# merkur-osdgruve-42.net
KiCad netlist of a schematic drawn in EAGLE
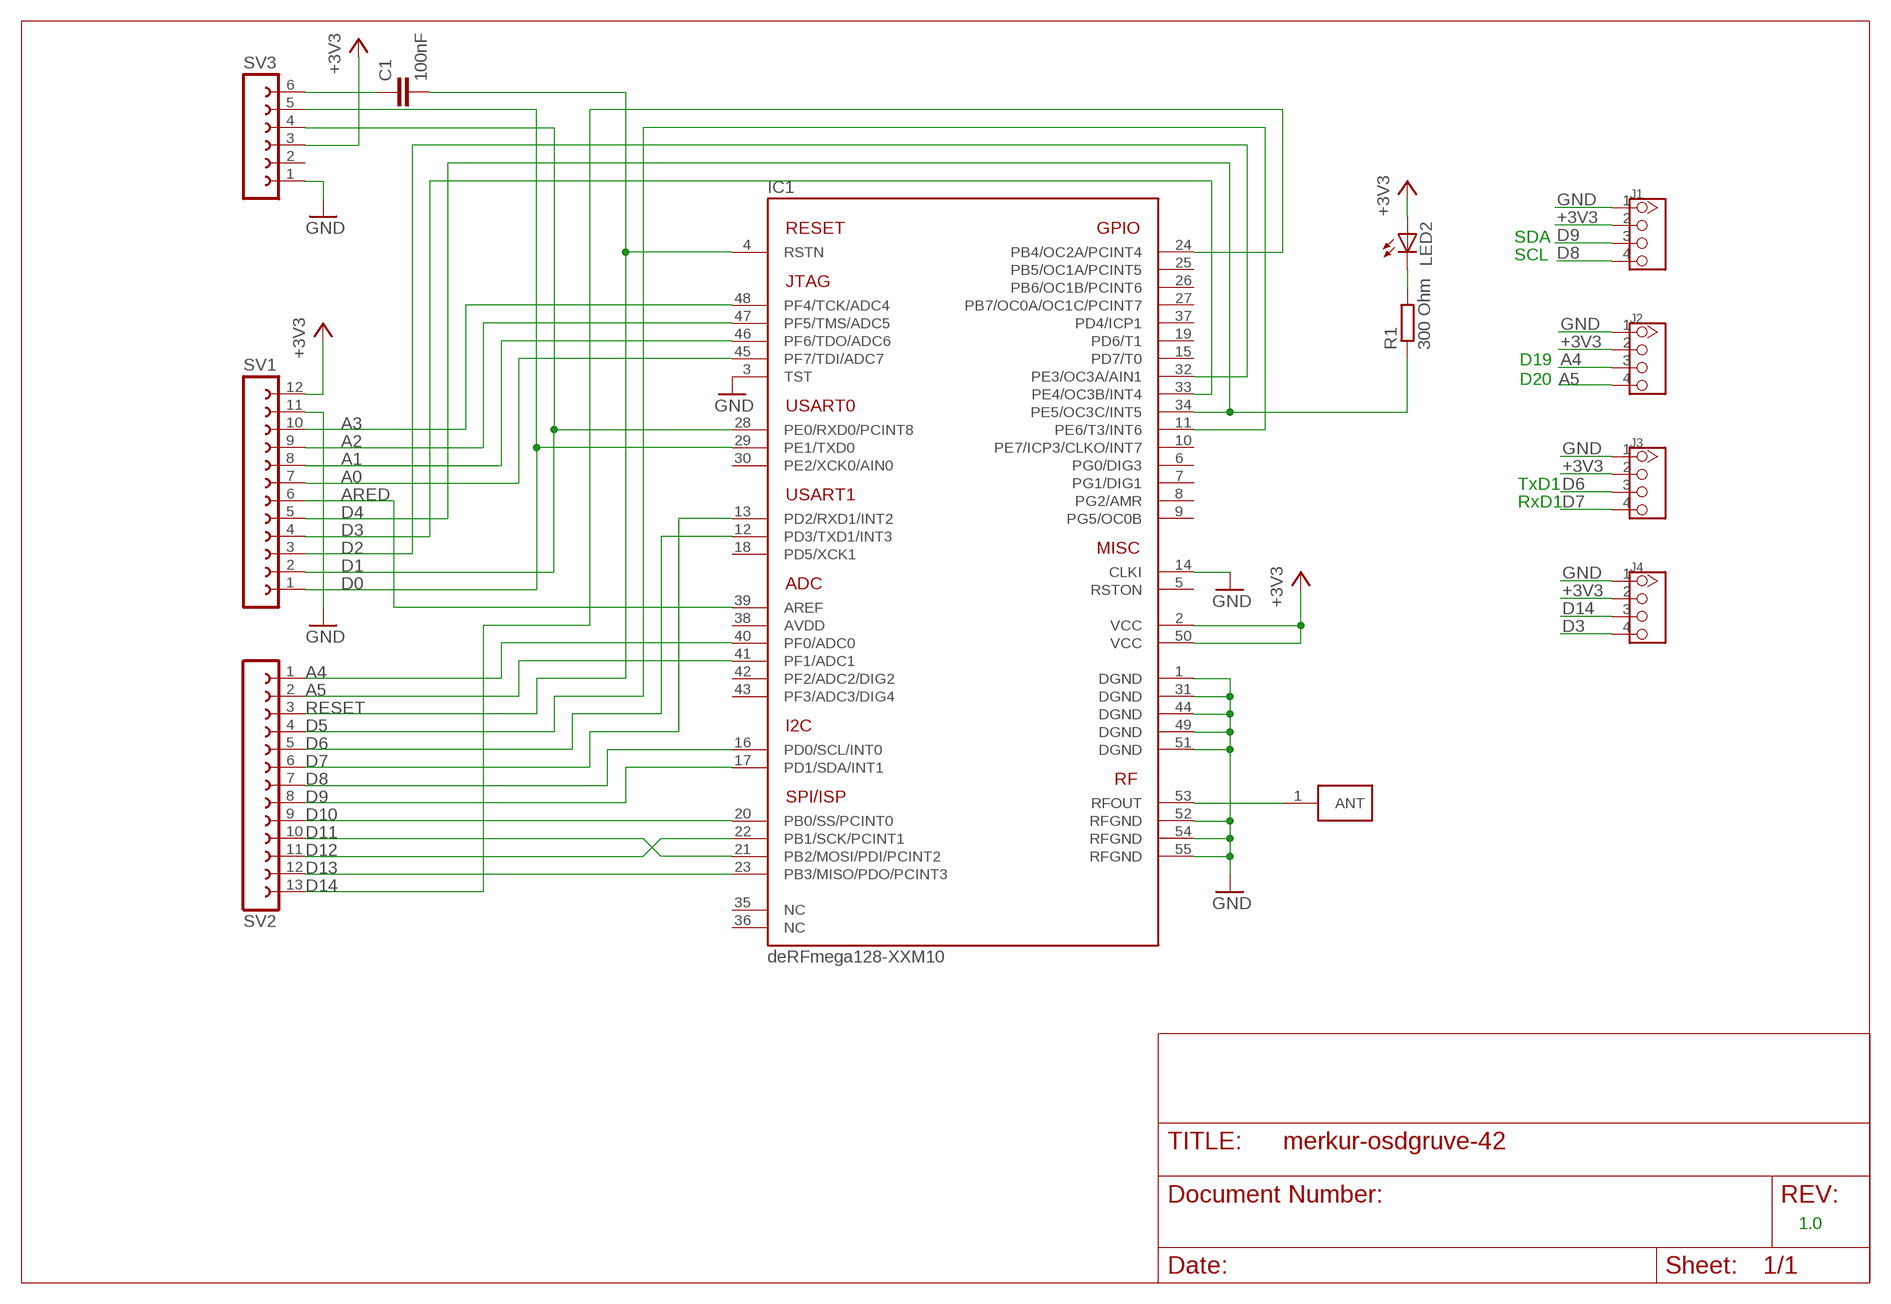
[diagram p0: schematic, sheet 1]

(export (version "E")
  (design (tool "Eeschema 10.0.6"))
  (components
    (comp (ref "C1")
      (value "100nF")
      (footprint "eagle-import:C0603")
      (libsource (lib "eagle-import") (part "C-EUC0603"))
    )
    (comp (ref "IC1")
      (value "DERFMEGA128-XXM10")
      (footprint "eagle-import:A-M10")
      (libsource (lib "eagle-import") (part "DERFMEGA128-XXM10"))
    )
    (comp (ref "J1")
      (value "CONNECTOR_TWIG-4P-2.0-2.0")
      (footprint "eagle-import:CONNECTOR_4P-2.0")
      (libsource (lib "eagle-import") (part "CONNECTOR_TWIG-4P-2.0-2.0"))
    )
    (comp (ref "J2")
      (value "CONNECTOR_TWIG-4P-2.0-2.0")
      (footprint "eagle-import:CONNECTOR_4P-2.0")
      (libsource (lib "eagle-import") (part "CONNECTOR_TWIG-4P-2.0-2.0"))
    )
    (comp (ref "J3")
      (value "CONNECTOR_TWIG-4P-2.0-2.0")
      (footprint "eagle-import:CONNECTOR_4P-2.0")
      (libsource (lib "eagle-import") (part "CONNECTOR_TWIG-4P-2.0-2.0"))
    )
    (comp (ref "J4")
      (value "CONNECTOR_TWIG-4P-2.0-2.0")
      (footprint "eagle-import:CONNECTOR_4P-2.0")
      (libsource (lib "eagle-import") (part "CONNECTOR_TWIG-4P-2.0-2.0"))
    )
    (comp (ref "LED2")
      (value "LEDCHIP-LED0603")
      (footprint "eagle-import:CHIP-LED0603")
      (libsource (lib "eagle-import") (part "LEDCHIP-LED0603"))
    )
    (comp (ref "R1")
      (value "300 Ohm")
      (footprint "eagle-import:R0603")
      (libsource (lib "eagle-import") (part "R-EU_R0603"))
    )
    (comp (ref "SV1")
      (value "FE12-1")
      (footprint "eagle-import:FE12")
      (libsource (lib "eagle-import") (part "FE12-1"))
    )
    (comp (ref "SV2")
      (value "FE13-1")
      (footprint "eagle-import:FE13")
      (libsource (lib "eagle-import") (part "FE13-1"))
    )
    (comp (ref "SV3")
      (value "FE06-1")
      (footprint "eagle-import:FE06")
      (libsource (lib "eagle-import") (part "FE06-1"))
    )
    (comp (ref "U$1")
      (value "PAD")
      (footprint "eagle-import:FE05-1")
      (libsource (lib "eagle-import") (part "PAD"))
    )
  )
  (nets
    (net (code "1") (name "+3V3") (class "Default")
      (node (ref "IC1") (pin "2") (pinfunction "VCC_2") (pintype "power_in"))
      (node (ref "IC1") (pin "50") (pinfunction "VCC_50") (pintype "power_in"))
      (node (ref "J1") (pin "2") (pinfunction "2_2") (pintype "bidirectional"))
      (node (ref "J2") (pin "2") (pinfunction "2_2") (pintype "bidirectional"))
      (node (ref "J3") (pin "2") (pinfunction "2_2") (pintype "bidirectional"))
      (node (ref "J4") (pin "2") (pinfunction "2_2") (pintype "bidirectional"))
      (node (ref "LED2") (pin "A") (pinfunction "A_A") (pintype "passive"))
      (node (ref "SV1") (pin "12") (pinfunction "12_12") (pintype "passive"))
      (node (ref "SV3") (pin "3") (pinfunction "3_3") (pintype "passive"))
    )
    (net (code "2") (name "/A0") (class "Default")
      (node (ref "IC1") (pin "45") (pinfunction "PF7/TDI/ADC7_45") (pintype "bidirectional"))
      (node (ref "SV1") (pin "7") (pinfunction "7_7") (pintype "passive"))
    )
    (net (code "3") (name "/A1") (class "Default")
      (node (ref "IC1") (pin "46") (pinfunction "PF6/TDO/ADC6_46") (pintype "bidirectional"))
      (node (ref "SV1") (pin "8") (pinfunction "8_8") (pintype "passive"))
    )
    (net (code "4") (name "/A2") (class "Default")
      (node (ref "IC1") (pin "47") (pinfunction "PF5/TMS/ADC5_47") (pintype "bidirectional"))
      (node (ref "SV1") (pin "9") (pinfunction "9_9") (pintype "passive"))
    )
    (net (code "5") (name "/A3") (class "Default")
      (node (ref "IC1") (pin "48") (pinfunction "PF4/TCK/ADC4_48") (pintype "bidirectional"))
      (node (ref "SV1") (pin "10") (pinfunction "10_10") (pintype "passive"))
    )
    (net (code "6") (name "/A4") (class "Default")
      (node (ref "IC1") (pin "40") (pinfunction "PF0/ADC0_40") (pintype "bidirectional"))
      (node (ref "J2") (pin "3") (pinfunction "3_3") (pintype "bidirectional"))
      (node (ref "SV2") (pin "1") (pinfunction "1_1") (pintype "passive"))
    )
    (net (code "7") (name "/A5") (class "Default")
      (node (ref "IC1") (pin "41") (pinfunction "PF1/ADC1_41") (pintype "bidirectional"))
      (node (ref "J2") (pin "4") (pinfunction "4_4") (pintype "bidirectional"))
      (node (ref "SV2") (pin "2") (pinfunction "2_2") (pintype "passive"))
    )
    (net (code "8") (name "/ARED") (class "Default")
      (node (ref "IC1") (pin "39") (pinfunction "AREF_39") (pintype "bidirectional"))
      (node (ref "SV1") (pin "6") (pinfunction "6_6") (pintype "passive"))
    )
    (net (code "9") (name "/AVDD") (class "Default")
      (node (ref "IC1") (pin "38") (pinfunction "AVDD_38") (pintype "power_in"))
    )
    (net (code "10") (name "/D0") (class "Default")
      (node (ref "IC1") (pin "29") (pinfunction "PE1/TXD0_29") (pintype "bidirectional"))
      (node (ref "SV1") (pin "1") (pinfunction "1_1") (pintype "passive"))
      (node (ref "SV3") (pin "5") (pinfunction "5_5") (pintype "passive"))
    )
    (net (code "11") (name "/D1") (class "Default")
      (node (ref "IC1") (pin "28") (pinfunction "PE0/RXD0/PCINT8_28") (pintype "bidirectional"))
      (node (ref "SV1") (pin "2") (pinfunction "2_2") (pintype "passive"))
      (node (ref "SV3") (pin "4") (pinfunction "4_4") (pintype "passive"))
    )
    (net (code "12") (name "/D2") (class "Default")
      (node (ref "IC1") (pin "32") (pinfunction "PE3/OC3A/AIN1_32") (pintype "bidirectional"))
      (node (ref "SV1") (pin "3") (pinfunction "3_3") (pintype "passive"))
    )
    (net (code "13") (name "/D3") (class "Default")
      (node (ref "IC1") (pin "33") (pinfunction "PE4/OC3B/INT4_33") (pintype "bidirectional"))
      (node (ref "J4") (pin "4") (pinfunction "4_4") (pintype "bidirectional"))
      (node (ref "SV1") (pin "4") (pinfunction "4_4") (pintype "passive"))
    )
    (net (code "14") (name "/D4") (class "Default")
      (node (ref "IC1") (pin "34") (pinfunction "PE5/OC3C/INT5_34") (pintype "bidirectional"))
      (node (ref "R1") (pin "1") (pinfunction "1_1") (pintype "passive"))
      (node (ref "SV1") (pin "5") (pinfunction "5_5") (pintype "passive"))
    )
    (net (code "15") (name "/D5") (class "Default")
      (node (ref "IC1") (pin "11") (pinfunction "PE6/T3/INT6_11") (pintype "bidirectional"))
      (node (ref "SV2") (pin "4") (pinfunction "4_4") (pintype "passive"))
    )
    (net (code "16") (name "/D6") (class "Default")
      (node (ref "IC1") (pin "12") (pinfunction "PD3/TXD1/INT3_12") (pintype "bidirectional"))
      (node (ref "J3") (pin "3") (pinfunction "3_3") (pintype "bidirectional"))
      (node (ref "SV2") (pin "5") (pinfunction "5_5") (pintype "passive"))
    )
    (net (code "17") (name "/D7") (class "Default")
      (node (ref "IC1") (pin "13") (pinfunction "PD2/RXD1/INT2_13") (pintype "bidirectional"))
      (node (ref "J3") (pin "4") (pinfunction "4_4") (pintype "bidirectional"))
      (node (ref "SV2") (pin "6") (pinfunction "6_6") (pintype "passive"))
    )
    (net (code "18") (name "/D8") (class "Default")
      (node (ref "IC1") (pin "16") (pinfunction "PD0/SCL/INT0_16") (pintype "bidirectional"))
      (node (ref "J1") (pin "4") (pinfunction "4_4") (pintype "bidirectional"))
      (node (ref "SV2") (pin "7") (pinfunction "7_7") (pintype "passive"))
    )
    (net (code "19") (name "/D9") (class "Default")
      (node (ref "IC1") (pin "17") (pinfunction "PD1/SDA/INT1_17") (pintype "bidirectional"))
      (node (ref "J1") (pin "3") (pinfunction "3_3") (pintype "bidirectional"))
      (node (ref "SV2") (pin "8") (pinfunction "8_8") (pintype "passive"))
    )
    (net (code "20") (name "/D10") (class "Default")
      (node (ref "IC1") (pin "20") (pinfunction "PB0/SS/PCINT0_20") (pintype "bidirectional"))
      (node (ref "SV2") (pin "9") (pinfunction "9_9") (pintype "passive"))
    )
    (net (code "21") (name "/D11") (class "Default")
      (node (ref "IC1") (pin "21") (pinfunction "PB2/MOSI/PDI/PCINT2_21") (pintype "bidirectional"))
      (node (ref "SV2") (pin "10") (pinfunction "10_10") (pintype "passive"))
    )
    (net (code "22") (name "/D12") (class "Default")
      (node (ref "IC1") (pin "22") (pinfunction "PB1/SCK/PCINT1_22") (pintype "bidirectional"))
      (node (ref "SV2") (pin "11") (pinfunction "11_11") (pintype "passive"))
    )
    (net (code "23") (name "/D13") (class "Default")
      (node (ref "IC1") (pin "23") (pinfunction "PB3/MISO/PDO/PCINT3_23") (pintype "bidirectional"))
      (node (ref "SV2") (pin "12") (pinfunction "12_12") (pintype "passive"))
    )
    (net (code "24") (name "/D14") (class "Default")
      (node (ref "IC1") (pin "24") (pinfunction "PB4/OC2A/PCINT4_24") (pintype "bidirectional"))
      (node (ref "J4") (pin "3") (pinfunction "3_3") (pintype "bidirectional"))
      (node (ref "SV2") (pin "13") (pinfunction "13_13") (pintype "passive"))
    )
    (net (code "25") (name "/RESET") (class "Default")
      (node (ref "C1") (pin "2") (pinfunction "2_2") (pintype "passive"))
      (node (ref "IC1") (pin "4") (pinfunction "RSTN_4") (pintype "input"))
      (node (ref "SV2") (pin "3") (pinfunction "3_3") (pintype "passive"))
    )
    (net (code "26") (name "GND") (class "Default")
      (node (ref "IC1") (pin "1") (pinfunction "DGND_1") (pintype "power_in"))
      (node (ref "IC1") (pin "14") (pinfunction "CLKI_14") (pintype "input"))
      (node (ref "IC1") (pin "3") (pinfunction "TST_3") (pintype "bidirectional"))
      (node (ref "IC1") (pin "31") (pinfunction "DGND_31") (pintype "power_in"))
      (node (ref "IC1") (pin "44") (pinfunction "DGND_44") (pintype "power_in"))
      (node (ref "IC1") (pin "49") (pinfunction "DGND_49") (pintype "power_in"))
      (node (ref "IC1") (pin "51") (pinfunction "DGND_51") (pintype "power_in"))
      (node (ref "IC1") (pin "52") (pinfunction "RFGND_52") (pintype "power_in"))
      (node (ref "IC1") (pin "54") (pinfunction "RFGND_54") (pintype "power_in"))
      (node (ref "IC1") (pin "55") (pinfunction "RFGND_55") (pintype "power_in"))
      (node (ref "J1") (pin "1") (pinfunction "1_1") (pintype "bidirectional"))
      (node (ref "J2") (pin "1") (pinfunction "1_1") (pintype "bidirectional"))
      (node (ref "J3") (pin "1") (pinfunction "1_1") (pintype "bidirectional"))
      (node (ref "J4") (pin "1") (pinfunction "1_1") (pintype "bidirectional"))
      (node (ref "SV1") (pin "11") (pinfunction "11_11") (pintype "passive"))
      (node (ref "SV3") (pin "1") (pinfunction "1_1") (pintype "passive"))
    )
    (net (code "27") (name "Net-(C1-Pad1)") (class "Default")
      (node (ref "C1") (pin "1") (pinfunction "1_1") (pintype "passive"))
      (node (ref "SV3") (pin "6") (pinfunction "6_6") (pintype "passive"))
    )
    (net (code "28") (name "Net-(IC1-RFOUT)") (class "Default")
      (node (ref "IC1") (pin "53") (pinfunction "RFOUT_53") (pintype "power_in"))
      (node (ref "U$1") (pin "1") (pinfunction "ANT_1") (pintype "output"))
    )
    (net (code "29") (name "Net-(LED2-PadC)") (class "Default")
      (node (ref "LED2") (pin "C") (pinfunction "C_C") (pintype "passive"))
      (node (ref "R1") (pin "2") (pinfunction "2_2") (pintype "passive"))
    )
    (net (code "30") (name "unconnected-(IC1-NC-Pad35)") (class "Default")
      (node (ref "IC1") (pin "35") (pinfunction "NC_35") (pintype "no_connect"))
    )
    (net (code "31") (name "unconnected-(IC1-NC-Pad36)") (class "Default")
      (node (ref "IC1") (pin "36") (pinfunction "NC_36") (pintype "no_connect"))
    )
    (net (code "32") (name "unconnected-(IC1-PB5{slash}OC1A{slash}PCINT5-Pad25)") (class "Default")
      (node (ref "IC1") (pin "25") (pinfunction "PB5/OC1A/PCINT5_25") (pintype "bidirectional"))
    )
    (net (code "33") (name "unconnected-(IC1-PB6{slash}OC1B{slash}PCINT6-Pad26)") (class "Default")
      (node (ref "IC1") (pin "26") (pinfunction "PB6/OC1B/PCINT6_26") (pintype "bidirectional"))
    )
    (net (code "34") (name "unconnected-(IC1-PB7{slash}OC0A{slash}OC1C{slash}PCINT7-Pad27)") (class "Default")
      (node (ref "IC1") (pin "27") (pinfunction "PB7/OC0A/OC1C/PCINT7_27") (pintype "bidirectional"))
    )
    (net (code "35") (name "unconnected-(IC1-PD4{slash}ICP1-Pad37)") (class "Default")
      (node (ref "IC1") (pin "37") (pinfunction "PD4/ICP1_37") (pintype "bidirectional"))
    )
    (net (code "36") (name "unconnected-(IC1-PD5{slash}XCK1-Pad18)") (class "Default")
      (node (ref "IC1") (pin "18") (pinfunction "PD5/XCK1_18") (pintype "bidirectional"))
    )
    (net (code "37") (name "unconnected-(IC1-PD6{slash}T1-Pad19)") (class "Default")
      (node (ref "IC1") (pin "19") (pinfunction "PD6/T1_19") (pintype "bidirectional"))
    )
    (net (code "38") (name "unconnected-(IC1-PD7{slash}T0-Pad15)") (class "Default")
      (node (ref "IC1") (pin "15") (pinfunction "PD7/T0_15") (pintype "bidirectional"))
    )
    (net (code "39") (name "unconnected-(IC1-PE2{slash}XCK0{slash}AIN0-Pad30)") (class "Default")
      (node (ref "IC1") (pin "30") (pinfunction "PE2/XCK0/AIN0_30") (pintype "bidirectional"))
    )
    (net (code "40") (name "unconnected-(IC1-PE7{slash}ICP3{slash}CLKO{slash}INT7-Pad10)") (class "Default")
      (node (ref "IC1") (pin "10") (pinfunction "PE7/ICP3/CLKO/INT7_10") (pintype "bidirectional"))
    )
    (net (code "41") (name "unconnected-(IC1-PF2{slash}ADC2{slash}DIG2-Pad42)") (class "Default")
      (node (ref "IC1") (pin "42") (pinfunction "PF2/ADC2/DIG2_42") (pintype "bidirectional"))
    )
    (net (code "42") (name "unconnected-(IC1-PF3{slash}ADC3{slash}DIG4-Pad43)") (class "Default")
      (node (ref "IC1") (pin "43") (pinfunction "PF3/ADC3/DIG4_43") (pintype "bidirectional"))
    )
    (net (code "43") (name "unconnected-(IC1-PG0{slash}DIG3-Pad6)") (class "Default")
      (node (ref "IC1") (pin "6") (pinfunction "PG0/DIG3_6") (pintype "bidirectional"))
    )
    (net (code "44") (name "unconnected-(IC1-PG1{slash}DIG1-Pad7)") (class "Default")
      (node (ref "IC1") (pin "7") (pinfunction "PG1/DIG1_7") (pintype "bidirectional"))
    )
    (net (code "45") (name "unconnected-(IC1-PG2{slash}AMR-Pad8)") (class "Default")
      (node (ref "IC1") (pin "8") (pinfunction "PG2/AMR_8") (pintype "bidirectional"))
    )
    (net (code "46") (name "unconnected-(IC1-PG5{slash}OC0B-Pad9)") (class "Default")
      (node (ref "IC1") (pin "9") (pinfunction "PG5/OC0B_9") (pintype "bidirectional"))
    )
    (net (code "47") (name "unconnected-(IC1-RSTON-Pad5)") (class "Default")
      (node (ref "IC1") (pin "5") (pinfunction "RSTON_5") (pintype "output"))
    )
    (net (code "48") (name "unconnected-(SV3-Pad2)") (class "Default")
      (node (ref "SV3") (pin "2") (pinfunction "2_2") (pintype "passive"))
    )
  )
)
